# RF.net
KiCad netlist of a schematic drawn in EAGLE
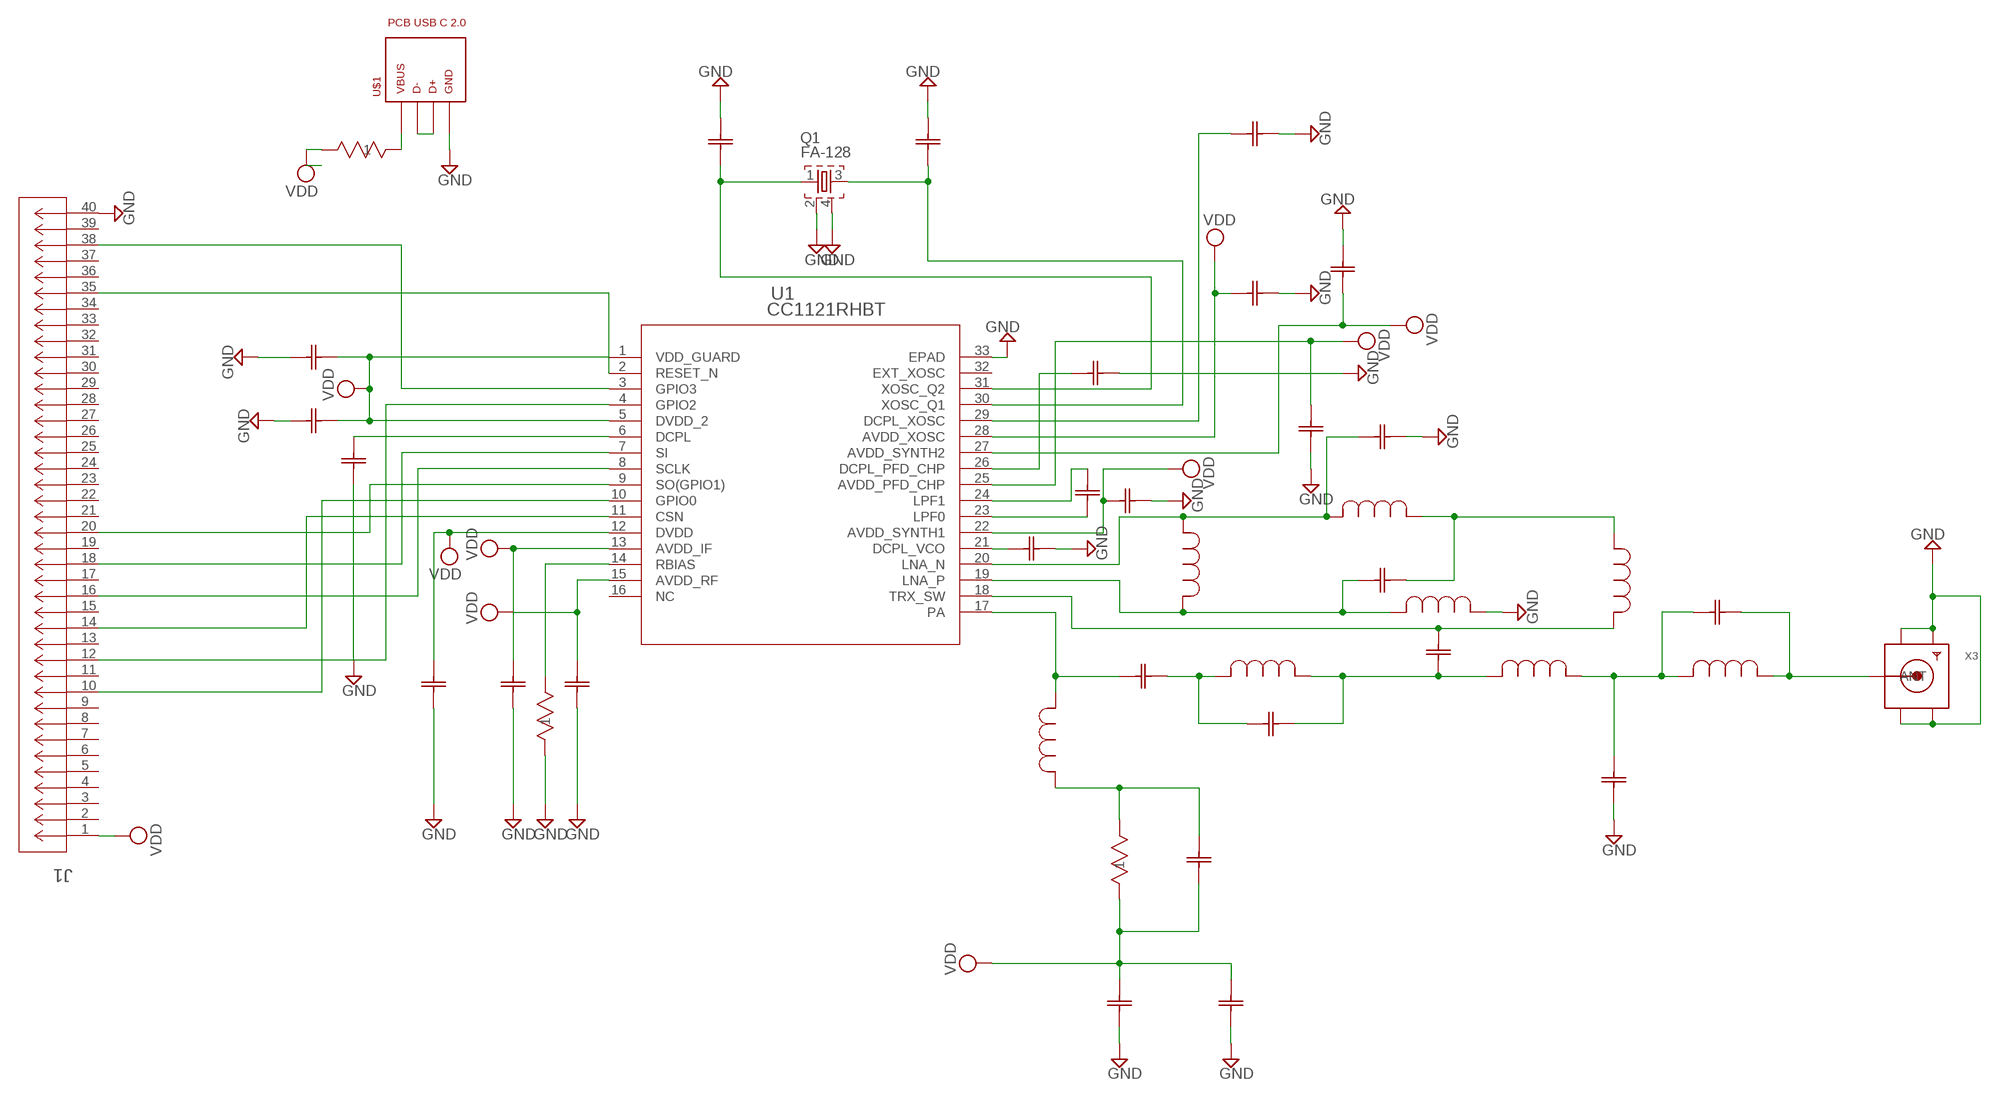
[diagram p0: schematic, sheet 1]

(export (version "E")
  (design (tool "Eeschema 10.0.6"))
  (components
    (comp (ref "C1")
      (value "220nF")
      (footprint "eagle-import:G-155_MUR")
      (fields
        (field (name "MANUFACTURER_PART_NUMBER") "GRM155R71A104KA01D")
        (field (name "COPYRIGHT") "Copyright (C) 2015 Accelerated Designs. All rights reserved")
      )
      (libsource (lib "eagle-import") (part "GRM155R71A104KA01D"))
    )
    (comp (ref "C2")
      (value "47nF")
      (footprint "eagle-import:G-155_MUR")
      (fields
        (field (name "MANUFACTURER_PART_NUMBER") "GRM155R71A104KA01D")
        (field (name "COPYRIGHT") "Copyright (C) 2015 Accelerated Designs. All rights reserved")
      )
      (libsource (lib "eagle-import") (part "GRM155R71A104KA01D"))
    )
    (comp (ref "C3")
      (value "15pF")
      (footprint "eagle-import:G-155_MUR")
      (fields
        (field (name "MANUFACTURER_PART_NUMBER") "GRM155R71A104KA01D")
        (field (name "COPYRIGHT") "Copyright (C) 2015 Accelerated Designs. All rights reserved")
      )
      (libsource (lib "eagle-import") (part "GRM155R71A104KA01D"))
    )
    (comp (ref "C4")
      (value "1pF")
      (footprint "eagle-import:G-155_MUR")
      (fields
        (field (name "MANUFACTURER_PART_NUMBER") "GRM155R71A104KA01D")
        (field (name "COPYRIGHT") "Copyright (C) 2015 Accelerated Designs. All rights reserved")
      )
      (libsource (lib "eagle-import") (part "GRM155R71A104KA01D"))
    )
    (comp (ref "C5")
      (value "2.2pF")
      (footprint "eagle-import:G-155_MUR")
      (fields
        (field (name "MANUFACTURER_PART_NUMBER") "GRM155R71A104KA01D")
        (field (name "COPYRIGHT") "Copyright (C) 2015 Accelerated Designs. All rights reserved")
      )
      (libsource (lib "eagle-import") (part "GRM155R71A104KA01D"))
    )
    (comp (ref "C6")
      (value "47nF")
      (footprint "eagle-import:G-155_MUR")
      (fields
        (field (name "MANUFACTURER_PART_NUMBER") "GRM155R71A104KA01D")
        (field (name "COPYRIGHT") "Copyright (C) 2015 Accelerated Designs. All rights reserved")
      )
      (libsource (lib "eagle-import") (part "GRM155R71A104KA01D"))
    )
    (comp (ref "C7")
      (value "47nF")
      (footprint "eagle-import:G-155_MUR")
      (fields
        (field (name "MANUFACTURER_PART_NUMBER") "GRM155R71A104KA01D")
        (field (name "COPYRIGHT") "Copyright (C) 2015 Accelerated Designs. All rights reserved")
      )
      (libsource (lib "eagle-import") (part "GRM155R71A104KA01D"))
    )
    (comp (ref "C8")
      (value "47nF")
      (footprint "eagle-import:G-155_MUR")
      (fields
        (field (name "MANUFACTURER_PART_NUMBER") "GRM155R71A104KA01D")
        (field (name "COPYRIGHT") "Copyright (C) 2015 Accelerated Designs. All rights reserved")
      )
      (libsource (lib "eagle-import") (part "GRM155R71A104KA01D"))
    )
    (comp (ref "C9")
      (value "220nF")
      (footprint "eagle-import:G-155_MUR")
      (fields
        (field (name "MANUFACTURER_PART_NUMBER") "GRM155R71A104KA01D")
        (field (name "COPYRIGHT") "Copyright (C) 2015 Accelerated Designs. All rights reserved")
      )
      (libsource (lib "eagle-import") (part "GRM155R71A104KA01D"))
    )
    (comp (ref "C10")
      (value "33pF")
      (footprint "eagle-import:G-155_MUR")
      (fields
        (field (name "MANUFACTURER_PART_NUMBER") "GRM155R71A104KA01D")
        (field (name "COPYRIGHT") "Copyright (C) 2015 Accelerated Designs. All rights reserved")
      )
      (libsource (lib "eagle-import") (part "GRM155R71A104KA01D"))
    )
    (comp (ref "C11")
      (value "10pF")
      (footprint "eagle-import:G-155_MUR")
      (fields
        (field (name "MANUFACTURER_PART_NUMBER") "GRM155R71A104KA01D")
        (field (name "COPYRIGHT") "Copyright (C) 2015 Accelerated Designs. All rights reserved")
      )
      (libsource (lib "eagle-import") (part "GRM155R71A104KA01D"))
    )
    (comp (ref "C12")
      (value "10pF")
      (footprint "eagle-import:G-155_MUR")
      (fields
        (field (name "MANUFACTURER_PART_NUMBER") "GRM155R71A104KA01D")
        (field (name "COPYRIGHT") "Copyright (C) 2015 Accelerated Designs. All rights reserved")
      )
      (libsource (lib "eagle-import") (part "GRM155R71A104KA01D"))
    )
    (comp (ref "C13")
      (value "3pF")
      (footprint "eagle-import:G-155_MUR")
      (fields
        (field (name "MANUFACTURER_PART_NUMBER") "GRM155R71A104KA01D")
        (field (name "COPYRIGHT") "Copyright (C) 2015 Accelerated Designs. All rights reserved")
      )
      (libsource (lib "eagle-import") (part "GRM155R71A104KA01D"))
    )
    (comp (ref "C14")
      (value "GRM155R71A104KA01D")
      (footprint "eagle-import:G-155_MUR")
      (fields (field (name "COPYRIGHT") "Copyright (C) 2015 Accelerated Designs. All rights reserved"))
      (libsource (lib "eagle-import") (part "GRM155R71A104KA01D"))
    )
    (comp (ref "C15")
      (value "3.3pF")
      (footprint "eagle-import:G-155_MUR")
      (fields
        (field (name "MANUFACTURER_PART_NUMBER") "GRM155R71A104KA01D")
        (field (name "COPYRIGHT") "Copyright (C) 2015 Accelerated Designs. All rights reserved")
      )
      (libsource (lib "eagle-import") (part "GRM155R71A104KA01D"))
    )
    (comp (ref "C16")
      (value "3.3pF")
      (footprint "eagle-import:G-155_MUR")
      (fields
        (field (name "MANUFACTURER_PART_NUMBER") "GRM155R71A104KA01D")
        (field (name "COPYRIGHT") "Copyright (C) 2015 Accelerated Designs. All rights reserved")
      )
      (libsource (lib "eagle-import") (part "GRM155R71A104KA01D"))
    )
    (comp (ref "C17")
      (value "10nF")
      (footprint "eagle-import:G-155_MUR")
      (fields
        (field (name "MANUFACTURER_PART_NUMBER") "GRM155R71A104KA01D")
        (field (name "COPYRIGHT") "Copyright (C) 2015 Accelerated Designs. All rights reserved")
      )
      (libsource (lib "eagle-import") (part "GRM155R71A104KA01D"))
    )
    (comp (ref "C18")
      (value "10nF")
      (footprint "eagle-import:G-155_MUR")
      (fields
        (field (name "MANUFACTURER_PART_NUMBER") "GRM155R71A104KA01D")
        (field (name "COPYRIGHT") "Copyright (C) 2015 Accelerated Designs. All rights reserved")
      )
      (libsource (lib "eagle-import") (part "GRM155R71A104KA01D"))
    )
    (comp (ref "C19")
      (value "1.8nF")
      (footprint "eagle-import:G-155_MUR")
      (fields
        (field (name "MANUFACTURER_PART_NUMBER") "GRM155R71A104KA01D")
        (field (name "COPYRIGHT") "Copyright (C) 2015 Accelerated Designs. All rights reserved")
      )
      (libsource (lib "eagle-import") (part "GRM155R71A104KA01D"))
    )
    (comp (ref "C20")
      (value "47nF")
      (footprint "eagle-import:G-155_MUR")
      (fields
        (field (name "MANUFACTURER_PART_NUMBER") "GRM155R71A104KA01D")
        (field (name "COPYRIGHT") "Copyright (C) 2015 Accelerated Designs. All rights reserved")
      )
      (libsource (lib "eagle-import") (part "GRM155R71A104KA01D"))
    )
    (comp (ref "C21")
      (value "47nF")
      (footprint "eagle-import:G-155_MUR")
      (fields
        (field (name "MANUFACTURER_PART_NUMBER") "GRM155R71A104KA01D")
        (field (name "COPYRIGHT") "Copyright (C) 2015 Accelerated Designs. All rights reserved")
      )
      (libsource (lib "eagle-import") (part "GRM155R71A104KA01D"))
    )
    (comp (ref "C22")
      (value "47nF")
      (footprint "eagle-import:G-155_MUR")
      (fields
        (field (name "MANUFACTURER_PART_NUMBER") "GRM155R71A104KA01D")
        (field (name "COPYRIGHT") "Copyright (C) 2015 Accelerated Designs. All rights reserved")
      )
      (libsource (lib "eagle-import") (part "GRM155R71A104KA01D"))
    )
    (comp (ref "C23")
      (value "47nF")
      (footprint "eagle-import:G-155_MUR")
      (fields
        (field (name "MANUFACTURER_PART_NUMBER") "GRM155R71A104KA01D")
        (field (name "COPYRIGHT") "Copyright (C) 2015 Accelerated Designs. All rights reserved")
      )
      (libsource (lib "eagle-import") (part "GRM155R71A104KA01D"))
    )
    (comp (ref "C24")
      (value "15pF")
      (footprint "eagle-import:G-155_MUR")
      (fields
        (field (name "MANUFACTURER_PART_NUMBER") "GRM155R71A104KA01D")
        (field (name "COPYRIGHT") "Copyright (C) 2015 Accelerated Designs. All rights reserved")
      )
      (libsource (lib "eagle-import") (part "GRM155R71A104KA01D"))
    )
    (comp (ref "C25")
      (value "15pF")
      (footprint "eagle-import:G-155_MUR")
      (fields
        (field (name "MANUFACTURER_PART_NUMBER") "GRM155R71A104KA01D")
        (field (name "COPYRIGHT") "Copyright (C) 2015 Accelerated Designs. All rights reserved")
      )
      (libsource (lib "eagle-import") (part "GRM155R71A104KA01D"))
    )
    (comp (ref "C26")
      (value "47nF")
      (footprint "eagle-import:G-155_MUR")
      (fields
        (field (name "MANUFACTURER_PART_NUMBER") "GRM155R71A104KA01D")
        (field (name "COPYRIGHT") "Copyright (C) 2015 Accelerated Designs. All rights reserved")
      )
      (libsource (lib "eagle-import") (part "GRM155R71A104KA01D"))
    )
    (comp (ref "J1")
      (value "CLT-110-02-L-D-BE")
      (footprint "eagle-import:CON20_2X10_DUME_CLT_SAI")
      (libsource (lib "eagle-import") (part "CLT-110-02-L-D-BE"))
    )
    (comp (ref "L1")
      (value "10nH")
      (footprint "eagle-import:IND_LQW15AN13NG00D_MUR")
      (fields
        (field (name "MANUFACTURER_PART_NUMBER") "LQW15AN13NG00D")
        (field (name "COPYRIGHT") "Copyright (C) 2018 Accelerated Designs. All rights reserved")
      )
      (libsource (lib "eagle-import") (part "LQW15AN13NG00D"))
    )
    (comp (ref "L2")
      (value "10nH")
      (footprint "eagle-import:IND_LQW15AN13NG00D_MUR")
      (fields
        (field (name "MANUFACTURER_PART_NUMBER") "LQW15AN13NG00D")
        (field (name "COPYRIGHT") "Copyright (C) 2018 Accelerated Designs. All rights reserved")
      )
      (libsource (lib "eagle-import") (part "LQW15AN13NG00D"))
    )
    (comp (ref "L3")
      (value "10nH")
      (footprint "eagle-import:IND_LQW15AN13NG00D_MUR")
      (fields
        (field (name "MANUFACTURER_PART_NUMBER") "LQW15AN13NG00D")
        (field (name "COPYRIGHT") "Copyright (C) 2018 Accelerated Designs. All rights reserved")
      )
      (libsource (lib "eagle-import") (part "LQW15AN13NG00D"))
    )
    (comp (ref "L4")
      (value "12nH")
      (footprint "eagle-import:IND_LQW15AN13NG00D_MUR")
      (fields
        (field (name "MANUFACTURER_PART_NUMBER") "LQW15AN13NG00D")
        (field (name "COPYRIGHT") "Copyright (C) 2018 Accelerated Designs. All rights reserved")
      )
      (libsource (lib "eagle-import") (part "LQW15AN13NG00D"))
    )
    (comp (ref "L5")
      (value "15nH")
      (footprint "eagle-import:IND_LQW15AN13NG00D_MUR")
      (fields
        (field (name "MANUFACTURER_PART_NUMBER") "LQW15AN13NG00D")
        (field (name "COPYRIGHT") "Copyright (C) 2018 Accelerated Designs. All rights reserved")
      )
      (libsource (lib "eagle-import") (part "LQW15AN13NG00D"))
    )
    (comp (ref "L6")
      (value "12nH")
      (footprint "eagle-import:IND_LQW15AN13NG00D_MUR")
      (fields
        (field (name "MANUFACTURER_PART_NUMBER") "LQW15AN13NG00D")
        (field (name "COPYRIGHT") "Copyright (C) 2018 Accelerated Designs. All rights reserved")
      )
      (libsource (lib "eagle-import") (part "LQW15AN13NG00D"))
    )
    (comp (ref "L7")
      (value "12nH")
      (footprint "eagle-import:IND_LQW15AN13NG00D_MUR")
      (fields
        (field (name "MANUFACTURER_PART_NUMBER") "LQW15AN13NG00D")
        (field (name "COPYRIGHT") "Copyright (C) 2018 Accelerated Designs. All rights reserved")
      )
      (libsource (lib "eagle-import") (part "LQW15AN13NG00D"))
    )
    (comp (ref "L8")
      (value "12nH")
      (footprint "eagle-import:IND_LQW15AN13NG00D_MUR")
      (fields
        (field (name "MANUFACTURER_PART_NUMBER") "LQW15AN13NG00D")
        (field (name "COPYRIGHT") "Copyright (C) 2018 Accelerated Designs. All rights reserved")
      )
      (libsource (lib "eagle-import") (part "LQW15AN13NG00D"))
    )
    (comp (ref "Q1")
      (value "FA-128")
      (footprint "eagle-import:FA-128")
      (libsource (lib "eagle-import") (part "FA-128"))
    )
    (comp (ref "R1")
      (value "56k")
      (footprint "eagle-import:RES_1E0402_1XP5_KOA")
      (fields
        (field (name "MANUFACTURER_PART_NUMBER") "RK73H1ETTP1003F")
        (field (name "COPYRIGHT") "Copyright (C) 2018 Accelerated Designs. All rights reserved")
      )
      (libsource (lib "eagle-import") (part "RK73H1ETTP1003F"))
    )
    (comp (ref "R2")
      (value "56k")
      (footprint "eagle-import:RES_1E0402_1XP5_KOA")
      (fields
        (field (name "MANUFACTURER_PART_NUMBER") "RK73H1ETTP1003F")
        (field (name "COPYRIGHT") "Copyright (C) 2018 Accelerated Designs. All rights reserved")
      )
      (libsource (lib "eagle-import") (part "RK73H1ETTP1003F"))
    )
    (comp (ref "R3")
      (value "56k")
      (footprint "eagle-import:RES_1E0402_1XP5_KOA")
      (fields
        (field (name "MANUFACTURER_PART_NUMBER") "RK73H1ETTP1003F")
        (field (name "COPYRIGHT") "Copyright (C) 2018 Accelerated Designs. All rights reserved")
      )
      (libsource (lib "eagle-import") (part "RK73H1ETTP1003F"))
    )
    (comp (ref "U$1")
      (value "PCB_USB_C_2.0DS_1")
      (footprint "eagle-import:USB_TYPE_C_DS_1")
      (libsource (lib "eagle-import") (part "PCB_USB_C_2.0DS_1"))
    )
    (comp (ref "U1")
      (value "CC1121RHBT")
      (footprint "eagle-import:RHB32_3P45X3P45_TEX")
      (libsource (lib "eagle-import") (part "CC1121RHBT"))
    )
    (comp (ref "X3")
      (value "SMACONNECTOR_EDGE")
      (footprint "eagle-import:SMA_EDGELAUNCH")
      (libsource (lib "eagle-import") (part "SMACONNECTOR_EDGE"))
    )
  )
  (nets
    (net (code "1") (name "GND") (class "Default")
      (node (ref "C1") (pin "1") (pinfunction "1_1") (pintype "passive"))
      (node (ref "C11") (pin "1") (pinfunction "1_1") (pintype "passive"))
      (node (ref "C12") (pin "1") (pinfunction "1_1") (pintype "passive"))
      (node (ref "C13") (pin "1") (pinfunction "1_1") (pintype "passive"))
      (node (ref "C16") (pin "2") (pinfunction "2_2") (pintype "passive"))
      (node (ref "C17") (pin "2") (pinfunction "2_2") (pintype "passive"))
      (node (ref "C18") (pin "2") (pinfunction "2_2") (pintype "passive"))
      (node (ref "C2") (pin "1") (pinfunction "1_1") (pintype "passive"))
      (node (ref "C20") (pin "1") (pinfunction "1_1") (pintype "passive"))
      (node (ref "C21") (pin "2") (pinfunction "2_2") (pintype "passive"))
      (node (ref "C22") (pin "2") (pinfunction "2_2") (pintype "passive"))
      (node (ref "C23") (pin "2") (pinfunction "2_2") (pintype "passive"))
      (node (ref "C24") (pin "2") (pinfunction "2_2") (pintype "passive"))
      (node (ref "C25") (pin "2") (pinfunction "2_2") (pintype "passive"))
      (node (ref "C26") (pin "2") (pinfunction "2_2") (pintype "passive"))
      (node (ref "C6") (pin "1") (pinfunction "1_1") (pintype "passive"))
      (node (ref "C7") (pin "1") (pinfunction "1_1") (pintype "passive"))
      (node (ref "C8") (pin "1") (pinfunction "1_1") (pintype "passive"))
      (node (ref "C9") (pin "1") (pinfunction "1_1") (pintype "passive"))
      (node (ref "J1") (pin "40") (pinfunction "40_40") (pintype "passive"))
      (node (ref "L8") (pin "1") (pinfunction "1_1") (pintype "passive"))
      (node (ref "Q1") (pin "2") (pinfunction "2_2") (pintype "passive"))
      (node (ref "Q1") (pin "4") (pinfunction "4_4") (pintype "passive"))
      (node (ref "R1") (pin "1") (pinfunction "1_1") (pintype "passive"))
      (node (ref "U$1") (pin "A1") (pinfunction "GND_A1") (pintype "bidirectional"))
      (node (ref "U$1") (pin "A12") (pinfunction "GND_A12") (pintype "bidirectional"))
      (node (ref "U$1") (pin "B1") (pinfunction "GND_B1") (pintype "bidirectional"))
      (node (ref "U$1") (pin "B12") (pinfunction "GND_B12") (pintype "bidirectional"))
      (node (ref "U1") (pin "33") (pinfunction "EPAD_33") (pintype "passive"))
      (node (ref "X3") (pin "GND@1") (pinfunction "GND4_GND@1") (pintype "power_in"))
      (node (ref "X3") (pin "GND@2") (pinfunction "GND3_GND@2") (pintype "power_in"))
      (node (ref "X3") (pin "GND@3") (pinfunction "GND2_GND@3") (pintype "power_in"))
      (node (ref "X3") (pin "GND@4") (pinfunction "GND1_GND@4") (pintype "power_in"))
    )
    (net (code "2") (name "Net-(C3-Pad2)") (class "Default")
      (node (ref "C3") (pin "2") (pinfunction "2_2") (pintype "passive"))
      (node (ref "C4") (pin "1") (pinfunction "1_1") (pintype "passive"))
      (node (ref "L2") (pin "2") (pinfunction "2_2") (pintype "passive"))
    )
    (net (code "3") (name "Net-(C4-Pad2)") (class "Default")
      (node (ref "C4") (pin "2") (pinfunction "2_2") (pintype "passive"))
      (node (ref "C5") (pin "1") (pinfunction "1_1") (pintype "passive"))
      (node (ref "L2") (pin "1") (pinfunction "1_1") (pintype "passive"))
      (node (ref "L3") (pin "2") (pinfunction "2_2") (pintype "passive"))
    )
    (net (code "4") (name "Net-(C10-Pad2)") (class "Default")
      (node (ref "C10") (pin "2") (pinfunction "2_2") (pintype "passive"))
      (node (ref "L1") (pin "2") (pinfunction "2_2") (pintype "passive"))
      (node (ref "R2") (pin "2") (pinfunction "2_2") (pintype "passive"))
    )
    (net (code "5") (name "Net-(C13-Pad2)") (class "Default")
      (node (ref "C13") (pin "2") (pinfunction "2_2") (pintype "passive"))
      (node (ref "C14") (pin "1") (pinfunction "1_1") (pintype "passive"))
      (node (ref "L3") (pin "1") (pinfunction "1_1") (pintype "passive"))
      (node (ref "L4") (pin "2") (pinfunction "2_2") (pintype "passive"))
    )
    (net (code "6") (name "Net-(C15-Pad2)") (class "Default")
      (node (ref "C15") (pin "2") (pinfunction "2_2") (pintype "passive"))
      (node (ref "L6") (pin "1") (pinfunction "1_1") (pintype "passive"))
      (node (ref "L7") (pin "2") (pinfunction "2_2") (pintype "passive"))
    )
    (net (code "7") (name "Net-(R3-Pad1)") (class "Default")
      (node (ref "R3") (pin "1") (pinfunction "1_1") (pintype "passive"))
      (node (ref "U$1") (pin "A4") (pinfunction "VBUS_A4") (pintype "bidirectional"))
      (node (ref "U$1") (pin "A9") (pinfunction "VBUS_A9") (pintype "bidirectional"))
      (node (ref "U$1") (pin "B4") (pinfunction "VBUS_B4") (pintype "bidirectional"))
      (node (ref "U$1") (pin "B9") (pinfunction "VBUS_B9") (pintype "bidirectional"))
    )
    (net (code "8") (name "Net-(U$1-D+-PadA6)") (class "Default")
      (node (ref "U$1") (pin "A6") (pinfunction "D+_A6") (pintype "bidirectional"))
      (node (ref "U$1") (pin "A7") (pinfunction "D-_A7") (pintype "bidirectional"))
      (node (ref "U$1") (pin "B6") (pinfunction "D+_B6") (pintype "bidirectional"))
      (node (ref "U$1") (pin "B7") (pinfunction "D-_B7") (pintype "bidirectional"))
    )
    (net (code "9") (name "Net-(U1-CSN)") (class "Default")
      (node (ref "J1") (pin "14") (pinfunction "14_14") (pintype "passive"))
      (node (ref "U1") (pin "11") (pinfunction "CSN_11") (pintype "input"))
    )
    (net (code "10") (name "Net-(U1-DCPL)") (class "Default")
      (node (ref "C9") (pin "2") (pinfunction "2_2") (pintype "passive"))
      (node (ref "U1") (pin "6") (pinfunction "DCPL_6") (pintype "power_in"))
    )
    (net (code "11") (name "Net-(U1-DCPL_PFD_CHP)") (class "Default")
      (node (ref "C21") (pin "1") (pinfunction "1_1") (pintype "passive"))
      (node (ref "U1") (pin "26") (pinfunction "DCPL_PFD_CHP_26") (pintype "power_in"))
    )
    (net (code "12") (name "Net-(U1-DCPL_VCO)") (class "Default")
      (node (ref "C17") (pin "1") (pinfunction "1_1") (pintype "passive"))
      (node (ref "U1") (pin "21") (pinfunction "DCPL_VCO_21") (pintype "power_in"))
    )
    (net (code "13") (name "Net-(U1-DCPL_XOSC)") (class "Default")
      (node (ref "C26") (pin "1") (pinfunction "1_1") (pintype "passive"))
      (node (ref "U1") (pin "29") (pinfunction "DCPL_XOSC_29") (pintype "power_in"))
    )
    (net (code "14") (name "Net-(U1-GPIO0)") (class "Default")
      (node (ref "J1") (pin "10") (pinfunction "10_10") (pintype "passive"))
      (node (ref "U1") (pin "10") (pinfunction "GPIO0_10") (pintype "bidirectional"))
    )
    (net (code "15") (name "Net-(U1-GPIO2)") (class "Default")
      (node (ref "J1") (pin "12") (pinfunction "12_12") (pintype "passive"))
      (node (ref "U1") (pin "4") (pinfunction "GPIO2_4") (pintype "bidirectional"))
    )
    (net (code "16") (name "Net-(U1-GPIO3)") (class "Default")
      (node (ref "J1") (pin "38") (pinfunction "38_38") (pintype "passive"))
      (node (ref "U1") (pin "3") (pinfunction "GPIO3_3") (pintype "bidirectional"))
    )
    (net (code "17") (name "Net-(U1-LNA_N)") (class "Default")
      (node (ref "C16") (pin "1") (pinfunction "1_1") (pintype "passive"))
      (node (ref "L5") (pin "2") (pinfunction "2_2") (pintype "passive"))
      (node (ref "L6") (pin "2") (pinfunction "2_2") (pintype "passive"))
      (node (ref "U1") (pin "20") (pinfunction "LNA_N_20") (pintype "passive"))
    )
    (net (code "18") (name "Net-(U1-LNA_P)") (class "Default")
      (node (ref "C15") (pin "1") (pinfunction "1_1") (pintype "passive"))
      (node (ref "L5") (pin "1") (pinfunction "1_1") (pintype "passive"))
      (node (ref "L8") (pin "2") (pinfunction "2_2") (pintype "passive"))
      (node (ref "U1") (pin "19") (pinfunction "LNA_P_19") (pintype "passive"))
    )
    (net (code "19") (name "Net-(U1-LPF0)") (class "Default")
      (node (ref "C19") (pin "1") (pinfunction "1_1") (pintype "passive"))
      (node (ref "U1") (pin "23") (pinfunction "LPF0_23") (pintype "passive"))
    )
    (net (code "20") (name "Net-(U1-LPF1)") (class "Default")
      (node (ref "C19") (pin "2") (pinfunction "2_2") (pintype "passive"))
      (node (ref "U1") (pin "24") (pinfunction "LPF1_24") (pintype "passive"))
    )
    (net (code "21") (name "Net-(U1-PA)") (class "Default")
      (node (ref "C3") (pin "1") (pinfunction "1_1") (pintype "passive"))
      (node (ref "L1") (pin "1") (pinfunction "1_1") (pintype "passive"))
      (node (ref "U1") (pin "17") (pinfunction "PA_17") (pintype "passive"))
    )
    (net (code "22") (name "Net-(U1-RBIAS)") (class "Default")
      (node (ref "R1") (pin "2") (pinfunction "2_2") (pintype "passive"))
      (node (ref "U1") (pin "14") (pinfunction "RBIAS_14") (pintype "passive"))
    )
    (net (code "23") (name "Net-(U1-RESET_N)") (class "Default")
      (node (ref "J1") (pin "35") (pinfunction "35_35") (pintype "passive"))
      (node (ref "U1") (pin "2") (pinfunction "RESET_N_2") (pintype "input"))
    )
    (net (code "24") (name "Net-(U1-SCLK)") (class "Default")
      (node (ref "J1") (pin "16") (pinfunction "16_16") (pintype "passive"))
      (node (ref "U1") (pin "8") (pinfunction "SCLK_8") (pintype "input"))
    )
    (net (code "25") (name "Net-(U1-SI)") (class "Default")
      (node (ref "J1") (pin "18") (pinfunction "18_18") (pintype "passive"))
      (node (ref "U1") (pin "7") (pinfunction "SI_7") (pintype "input"))
    )
    (net (code "26") (name "Net-(U1-SO(GPIO1))") (class "Default")
      (node (ref "J1") (pin "20") (pinfunction "20_20") (pintype "passive"))
      (node (ref "U1") (pin "9") (pinfunction "SO(GPIO1)_9") (pintype "bidirectional"))
    )
    (net (code "27") (name "Net-(U1-TRX_SW)") (class "Default")
      (node (ref "C5") (pin "2") (pinfunction "2_2") (pintype "passive"))
      (node (ref "L7") (pin "1") (pinfunction "1_1") (pintype "passive"))
      (node (ref "U1") (pin "18") (pinfunction "TRX_SW_18") (pintype "passive"))
    )
    (net (code "28") (name "Net-(U1-XOSC_Q1)") (class "Default")
      (node (ref "C25") (pin "1") (pinfunction "1_1") (pintype "passive"))
      (node (ref "Q1") (pin "3") (pinfunction "3_3") (pintype "passive"))
      (node (ref "U1") (pin "30") (pinfunction "XOSC_Q1_30") (pintype "passive"))
    )
    (net (code "29") (name "Net-(U1-XOSC_Q2)") (class "Default")
      (node (ref "C24") (pin "1") (pinfunction "1_1") (pintype "passive"))
      (node (ref "Q1") (pin "1") (pinfunction "1_1") (pintype "passive"))
      (node (ref "U1") (pin "31") (pinfunction "XOSC_Q2_31") (pintype "passive"))
    )
    (net (code "30") (name "Net-(X3-ANT)") (class "Default")
      (node (ref "C14") (pin "2") (pinfunction "2_2") (pintype "passive"))
      (node (ref "L4") (pin "1") (pinfunction "1_1") (pintype "passive"))
      (node (ref "X3") (pin "P") (pinfunction "ANT_P") (pintype "bidirectional"))
    )
    (net (code "31") (name "VDD") (class "Default")
      (node (ref "C1") (pin "2") (pinfunction "2_2") (pintype "passive"))
      (node (ref "C10") (pin "1") (pinfunction "1_1") (pintype "passive"))
      (node (ref "C11") (pin "2") (pinfunction "2_2") (pintype "passive"))
      (node (ref "C12") (pin "2") (pinfunction "2_2") (pintype "passive"))
      (node (ref "C18") (pin "1") (pinfunction "1_1") (pintype "passive"))
      (node (ref "C2") (pin "2") (pinfunction "2_2") (pintype "passive"))
      (node (ref "C20") (pin "2") (pinfunction "2_2") (pintype "passive"))
      (node (ref "C22") (pin "1") (pinfunction "1_1") (pintype "passive"))
      (node (ref "C23") (pin "1") (pinfunction "1_1") (pintype "passive"))
      (node (ref "C6") (pin "2") (pinfunction "2_2") (pintype "passive"))
      (node (ref "C7") (pin "2") (pinfunction "2_2") (pintype "passive"))
      (node (ref "C8") (pin "2") (pinfunction "2_2") (pintype "passive"))
      (node (ref "J1") (pin "1") (pinfunction "1_1") (pintype "passive"))
      (node (ref "R2") (pin "1") (pinfunction "1_1") (pintype "passive"))
      (node (ref "R3") (pin "2") (pinfunction "2_2") (pintype "passive"))
      (node (ref "U1") (pin "1") (pinfunction "VDD_GUARD_1") (pintype "power_in"))
      (node (ref "U1") (pin "12") (pinfunction "DVDD_12") (pintype "power_in"))
      (node (ref "U1") (pin "13") (pinfunction "AVDD_IF_13") (pintype "power_in"))
      (node (ref "U1") (pin "15") (pinfunction "AVDD_RF_15") (pintype "power_in"))
      (node (ref "U1") (pin "22") (pinfunction "AVDD_SYNTH1_22") (pintype "power_in"))
      (node (ref "U1") (pin "25") (pinfunction "AVDD_PFD_CHP_25") (pintype "power_in"))
      (node (ref "U1") (pin "27") (pinfunction "AVDD_SYNTH2_27") (pintype "power_in"))
      (node (ref "U1") (pin "28") (pinfunction "AVDD_XOSC_28") (pintype "power_in"))
      (node (ref "U1") (pin "5") (pinfunction "DVDD_2_5") (pintype "power_in"))
    )
    (net (code "32") (name "unconnected-(J1-Pad2)") (class "Default")
      (node (ref "J1") (pin "2") (pinfunction "2_2") (pintype "passive"))
    )
    (net (code "33") (name "unconnected-(J1-Pad3)") (class "Default")
      (node (ref "J1") (pin "3") (pinfunction "3_3") (pintype "passive"))
    )
    (net (code "34") (name "unconnected-(J1-Pad4)") (class "Default")
      (node (ref "J1") (pin "4") (pinfunction "4_4") (pintype "passive"))
    )
    (net (code "35") (name "unconnected-(J1-Pad5)") (class "Default")
      (node (ref "J1") (pin "5") (pinfunction "5_5") (pintype "passive"))
    )
    (net (code "36") (name "unconnected-(J1-Pad6)") (class "Default")
      (node (ref "J1") (pin "6") (pinfunction "6_6") (pintype "passive"))
    )
    (net (code "37") (name "unconnected-(J1-Pad7)") (class "Default")
      (node (ref "J1") (pin "7") (pinfunction "7_7") (pintype "passive"))
    )
    (net (code "38") (name "unconnected-(J1-Pad8)") (class "Default")
      (node (ref "J1") (pin "8") (pinfunction "8_8") (pintype "passive"))
    )
    (net (code "39") (name "unconnected-(J1-Pad9)") (class "Default")
      (node (ref "J1") (pin "9") (pinfunction "9_9") (pintype "passive"))
    )
    (net (code "40") (name "unconnected-(J1-Pad11)") (class "Default")
      (node (ref "J1") (pin "11") (pinfunction "11_11") (pintype "passive"))
    )
    (net (code "41") (name "unconnected-(J1-Pad13)") (class "Default")
      (node (ref "J1") (pin "13") (pinfunction "13_13") (pintype "passive"))
    )
    (net (code "42") (name "unconnected-(J1-Pad15)") (class "Default")
      (node (ref "J1") (pin "15") (pinfunction "15_15") (pintype "passive"))
    )
    (net (code "43") (name "unconnected-(J1-Pad17)") (class "Default")
      (node (ref "J1") (pin "17") (pinfunction "17_17") (pintype "passive"))
    )
    (net (code "44") (name "unconnected-(J1-Pad19)") (class "Default")
      (node (ref "J1") (pin "19") (pinfunction "19_19") (pintype "passive"))
    )
    (net (code "45") (name "unconnected-(J1-Pad21)") (class "Default")
      (node (ref "J1") (pin "21") (pinfunction "21_21") (pintype "passive"))
    )
    (net (code "46") (name "unconnected-(J1-Pad22)") (class "Default")
      (node (ref "J1") (pin "22") (pinfunction "22_22") (pintype "passive"))
    )
    (net (code "47") (name "unconnected-(J1-Pad23)") (class "Default")
      (node (ref "J1") (pin "23") (pinfunction "23_23") (pintype "passive"))
    )
    (net (code "48") (name "unconnected-(J1-Pad24)") (class "Default")
      (node (ref "J1") (pin "24") (pinfunction "24_24") (pintype "passive"))
    )
    (net (code "49") (name "unconnected-(J1-Pad25)") (class "Default")
      (node (ref "J1") (pin "25") (pinfunction "25_25") (pintype "passive"))
    )
    (net (code "50") (name "unconnected-(J1-Pad26)") (class "Default")
      (node (ref "J1") (pin "26") (pinfunction "26_26") (pintype "passive"))
    )
    (net (code "51") (name "unconnected-(J1-Pad27)") (class "Default")
      (node (ref "J1") (pin "27") (pinfunction "27_27") (pintype "passive"))
    )
    (net (code "52") (name "unconnected-(J1-Pad28)") (class "Default")
      (node (ref "J1") (pin "28") (pinfunction "28_28") (pintype "passive"))
    )
    (net (code "53") (name "unconnected-(J1-Pad29)") (class "Default")
      (node (ref "J1") (pin "29") (pinfunction "29_29") (pintype "passive"))
    )
    (net (code "54") (name "unconnected-(J1-Pad30)") (class "Default")
      (node (ref "J1") (pin "30") (pinfunction "30_30") (pintype "passive"))
    )
    (net (code "55") (name "unconnected-(J1-Pad31)") (class "Default")
      (node (ref "J1") (pin "31") (pinfunction "31_31") (pintype "passive"))
    )
    (net (code "56") (name "unconnected-(J1-Pad32)") (class "Default")
      (node (ref "J1") (pin "32") (pinfunction "32_32") (pintype "passive"))
    )
    (net (code "57") (name "unconnected-(J1-Pad33)") (class "Default")
      (node (ref "J1") (pin "33") (pinfunction "33_33") (pintype "passive"))
    )
    (net (code "58") (name "unconnected-(J1-Pad34)") (class "Default")
      (node (ref "J1") (pin "34") (pinfunction "34_34") (pintype "passive"))
    )
    (net (code "59") (name "unconnected-(J1-Pad36)") (class "Default")
      (node (ref "J1") (pin "36") (pinfunction "36_36") (pintype "passive"))
    )
    (net (code "60") (name "unconnected-(J1-Pad37)") (class "Default")
      (node (ref "J1") (pin "37") (pinfunction "37_37") (pintype "passive"))
    )
    (net (code "61") (name "unconnected-(J1-Pad39)") (class "Default")
      (node (ref "J1") (pin "39") (pinfunction "39_39") (pintype "passive"))
    )
    (net (code "62") (name "unconnected-(U1-EXT_XOSC-Pad32)") (class "Default")
      (node (ref "U1") (pin "32") (pinfunction "EXT_XOSC_32") (pintype "input"))
    )
    (net (code "63") (name "unconnected-(U1-NC-Pad16)") (class "Default")
      (node (ref "U1") (pin "16") (pinfunction "NC_16") (pintype "no_connect"))
    )
  )
)
